# arduino_backpack.net
KiCad netlist of a schematic drawn in EAGLE
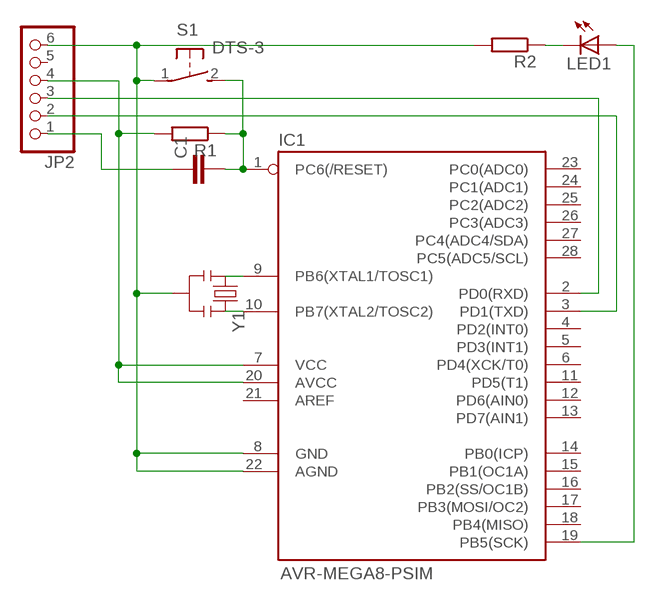
[diagram p0: schematic, sheet 1]

(export (version "E")
  (design (tool "Eeschema 10.0.6"))
  (components
    (comp (ref "C1")
      (value "C-EU025-025X050")
      (footprint "eagle-import:C025-025X050")
      (libsource (lib "eagle-import") (part "C-EU025-025X050"))
    )
    (comp (ref "IC1")
      (value "AVR-MEGA8-PSIM")
      (footprint "eagle-import:DIL28-3-SIMON")
      (libsource (lib "eagle-import") (part "AVR-MEGA8-PSIM"))
    )
    (comp (ref "JP2")
      (value "PINHD-1X6")
      (footprint "eagle-import:1X06")
      (libsource (lib "eagle-import") (part "PINHD-1X6"))
    )
    (comp (ref "LED1")
      (value "LED3MM")
      (footprint "eagle-import:LED3MM")
      (libsource (lib "eagle-import") (part "LED3MM"))
    )
    (comp (ref "R1")
      (value "R-EU_0204/2V")
      (footprint "eagle-import:0204V")
      (libsource (lib "eagle-import") (part "R-EU_0204/2V"))
    )
    (comp (ref "R2")
      (value "R-EU_0204/2V")
      (footprint "eagle-import:0204V")
      (libsource (lib "eagle-import") (part "R-EU_0204/2V"))
    )
    (comp (ref "S1")
      (value "DTS-3")
      (footprint "eagle-import:DTS-3")
      (libsource (lib "eagle-import") (part "DTS-3"))
    )
    (comp (ref "Y1")
      (value "RESONATORPTH")
      (footprint "eagle-import:RESONATOR-PTH")
      (libsource (lib "eagle-import") (part "RESONATORPTH"))
    )
  )
  (nets
    (net (code "1") (name "Net-(C1-Pad1)") (class "Default")
      (node (ref "C1") (pin "1") (pinfunction "1_1") (pintype "passive"))
      (node (ref "JP2") (pin "1") (pinfunction "1_1") (pintype "passive"))
    )
    (net (code "2") (name "Net-(IC1-AGND)") (class "Default")
      (node (ref "IC1") (pin "22") (pinfunction "AGND_22") (pintype "bidirectional"))
      (node (ref "IC1") (pin "8") (pinfunction "GND_8") (pintype "bidirectional"))
      (node (ref "JP2") (pin "6") (pinfunction "6_6") (pintype "passive"))
      (node (ref "R2") (pin "2") (pinfunction "2_2") (pintype "passive"))
      (node (ref "S1") (pin "1") (pinfunction "1_1") (pintype "passive"))
      (node (ref "Y1") (pin "2") (pinfunction "2_2") (pintype "passive"))
    )
    (net (code "3") (name "Net-(IC1-AVCC)") (class "Default")
      (node (ref "IC1") (pin "20") (pinfunction "AVCC_20") (pintype "bidirectional"))
      (node (ref "IC1") (pin "7") (pinfunction "VCC_7") (pintype "bidirectional"))
      (node (ref "JP2") (pin "4") (pinfunction "4_4") (pintype "passive"))
      (node (ref "R1") (pin "2") (pinfunction "2_2") (pintype "passive"))
    )
    (net (code "4") (name "Net-(IC1-PB5(SCK))") (class "Default")
      (node (ref "IC1") (pin "19") (pinfunction "PB5(SCK)_19") (pintype "bidirectional"))
      (node (ref "LED1") (pin "A") (pinfunction "A_A") (pintype "passive"))
    )
    (net (code "5") (name "Net-(IC1-PB6(XTAL1{slash}TOSC1))") (class "Default")
      (node (ref "IC1") (pin "9") (pinfunction "PB6(XTAL1/TOSC1)_9") (pintype "bidirectional"))
      (node (ref "Y1") (pin "1") (pinfunction "1_1") (pintype "passive"))
    )
    (net (code "6") (name "Net-(IC1-PB7(XTAL2{slash}TOSC2))") (class "Default")
      (node (ref "IC1") (pin "10") (pinfunction "PB7(XTAL2/TOSC2)_10") (pintype "bidirectional"))
      (node (ref "Y1") (pin "3") (pinfunction "3_3") (pintype "passive"))
    )
    (net (code "7") (name "Net-(IC1-PC6({slash}RESET))") (class "Default")
      (node (ref "C1") (pin "2") (pinfunction "2_2") (pintype "passive"))
      (node (ref "IC1") (pin "1") (pinfunction "PC6(/RESET)_1") (pintype "bidirectional"))
      (node (ref "R1") (pin "1") (pinfunction "1_1") (pintype "passive"))
      (node (ref "S1") (pin "2") (pinfunction "2_2") (pintype "passive"))
    )
    (net (code "8") (name "Net-(IC1-PD0(RXD))") (class "Default")
      (node (ref "IC1") (pin "2") (pinfunction "PD0(RXD)_2") (pintype "bidirectional"))
      (node (ref "JP2") (pin "3") (pinfunction "3_3") (pintype "passive"))
    )
    (net (code "9") (name "Net-(IC1-PD1(TXD))") (class "Default")
      (node (ref "IC1") (pin "3") (pinfunction "PD1(TXD)_3") (pintype "bidirectional"))
      (node (ref "JP2") (pin "2") (pinfunction "2_2") (pintype "passive"))
    )
    (net (code "10") (name "Net-(LED1-C)") (class "Default")
      (node (ref "LED1") (pin "K") (pinfunction "C_K") (pintype "passive"))
      (node (ref "R2") (pin "1") (pinfunction "1_1") (pintype "passive"))
    )
    (net (code "11") (name "unconnected-(IC1-AREF-Pad21)") (class "Default")
      (node (ref "IC1") (pin "21") (pinfunction "AREF_21") (pintype "bidirectional"))
    )
    (net (code "12") (name "unconnected-(IC1-PB0(ICP)-Pad14)") (class "Default")
      (node (ref "IC1") (pin "14") (pinfunction "PB0(ICP)_14") (pintype "bidirectional"))
    )
    (net (code "13") (name "unconnected-(IC1-PB1(OC1A)-Pad15)") (class "Default")
      (node (ref "IC1") (pin "15") (pinfunction "PB1(OC1A)_15") (pintype "bidirectional"))
    )
    (net (code "14") (name "unconnected-(IC1-PB2(SS{slash}OC1B)-Pad16)") (class "Default")
      (node (ref "IC1") (pin "16") (pinfunction "PB2(SS/OC1B)_16") (pintype "bidirectional"))
    )
    (net (code "15") (name "unconnected-(IC1-PB3(MOSI{slash}OC2)-Pad17)") (class "Default")
      (node (ref "IC1") (pin "17") (pinfunction "PB3(MOSI/OC2)_17") (pintype "bidirectional"))
    )
    (net (code "16") (name "unconnected-(IC1-PB4(MISO)-Pad18)") (class "Default")
      (node (ref "IC1") (pin "18") (pinfunction "PB4(MISO)_18") (pintype "bidirectional"))
    )
    (net (code "17") (name "unconnected-(IC1-PC0(ADC0)-Pad23)") (class "Default")
      (node (ref "IC1") (pin "23") (pinfunction "PC0(ADC0)_23") (pintype "bidirectional"))
    )
    (net (code "18") (name "unconnected-(IC1-PC1(ADC1)-Pad24)") (class "Default")
      (node (ref "IC1") (pin "24") (pinfunction "PC1(ADC1)_24") (pintype "bidirectional"))
    )
    (net (code "19") (name "unconnected-(IC1-PC2(ADC2)-Pad25)") (class "Default")
      (node (ref "IC1") (pin "25") (pinfunction "PC2(ADC2)_25") (pintype "bidirectional"))
    )
    (net (code "20") (name "unconnected-(IC1-PC3(ADC3)-Pad26)") (class "Default")
      (node (ref "IC1") (pin "26") (pinfunction "PC3(ADC3)_26") (pintype "bidirectional"))
    )
    (net (code "21") (name "unconnected-(IC1-PC4(ADC4{slash}SDA)-Pad27)") (class "Default")
      (node (ref "IC1") (pin "27") (pinfunction "PC4(ADC4/SDA)_27") (pintype "bidirectional"))
    )
    (net (code "22") (name "unconnected-(IC1-PC5(ADC5{slash}SCL)-Pad28)") (class "Default")
      (node (ref "IC1") (pin "28") (pinfunction "PC5(ADC5/SCL)_28") (pintype "bidirectional"))
    )
    (net (code "23") (name "unconnected-(IC1-PD2(INT0)-Pad4)") (class "Default")
      (node (ref "IC1") (pin "4") (pinfunction "PD2(INT0)_4") (pintype "bidirectional"))
    )
    (net (code "24") (name "unconnected-(IC1-PD3(INT1)-Pad5)") (class "Default")
      (node (ref "IC1") (pin "5") (pinfunction "PD3(INT1)_5") (pintype "bidirectional"))
    )
    (net (code "25") (name "unconnected-(IC1-PD4(XCK{slash}T0)-Pad6)") (class "Default")
      (node (ref "IC1") (pin "6") (pinfunction "PD4(XCK/T0)_6") (pintype "bidirectional"))
    )
    (net (code "26") (name "unconnected-(IC1-PD5(T1)-Pad11)") (class "Default")
      (node (ref "IC1") (pin "11") (pinfunction "PD5(T1)_11") (pintype "bidirectional"))
    )
    (net (code "27") (name "unconnected-(IC1-PD6(AIN0)-Pad12)") (class "Default")
      (node (ref "IC1") (pin "12") (pinfunction "PD6(AIN0)_12") (pintype "bidirectional"))
    )
    (net (code "28") (name "unconnected-(IC1-PD7(AIN1)-Pad13)") (class "Default")
      (node (ref "IC1") (pin "13") (pinfunction "PD7(AIN1)_13") (pintype "bidirectional"))
    )
    (net (code "29") (name "unconnected-(JP2-Pad5)") (class "Default")
      (node (ref "JP2") (pin "5") (pinfunction "5_5") (pintype "passive"))
    )
  )
)
